# JTAG_DEBUG_HEADERS.net
KiCad netlist of a schematic drawn in Altium Designer
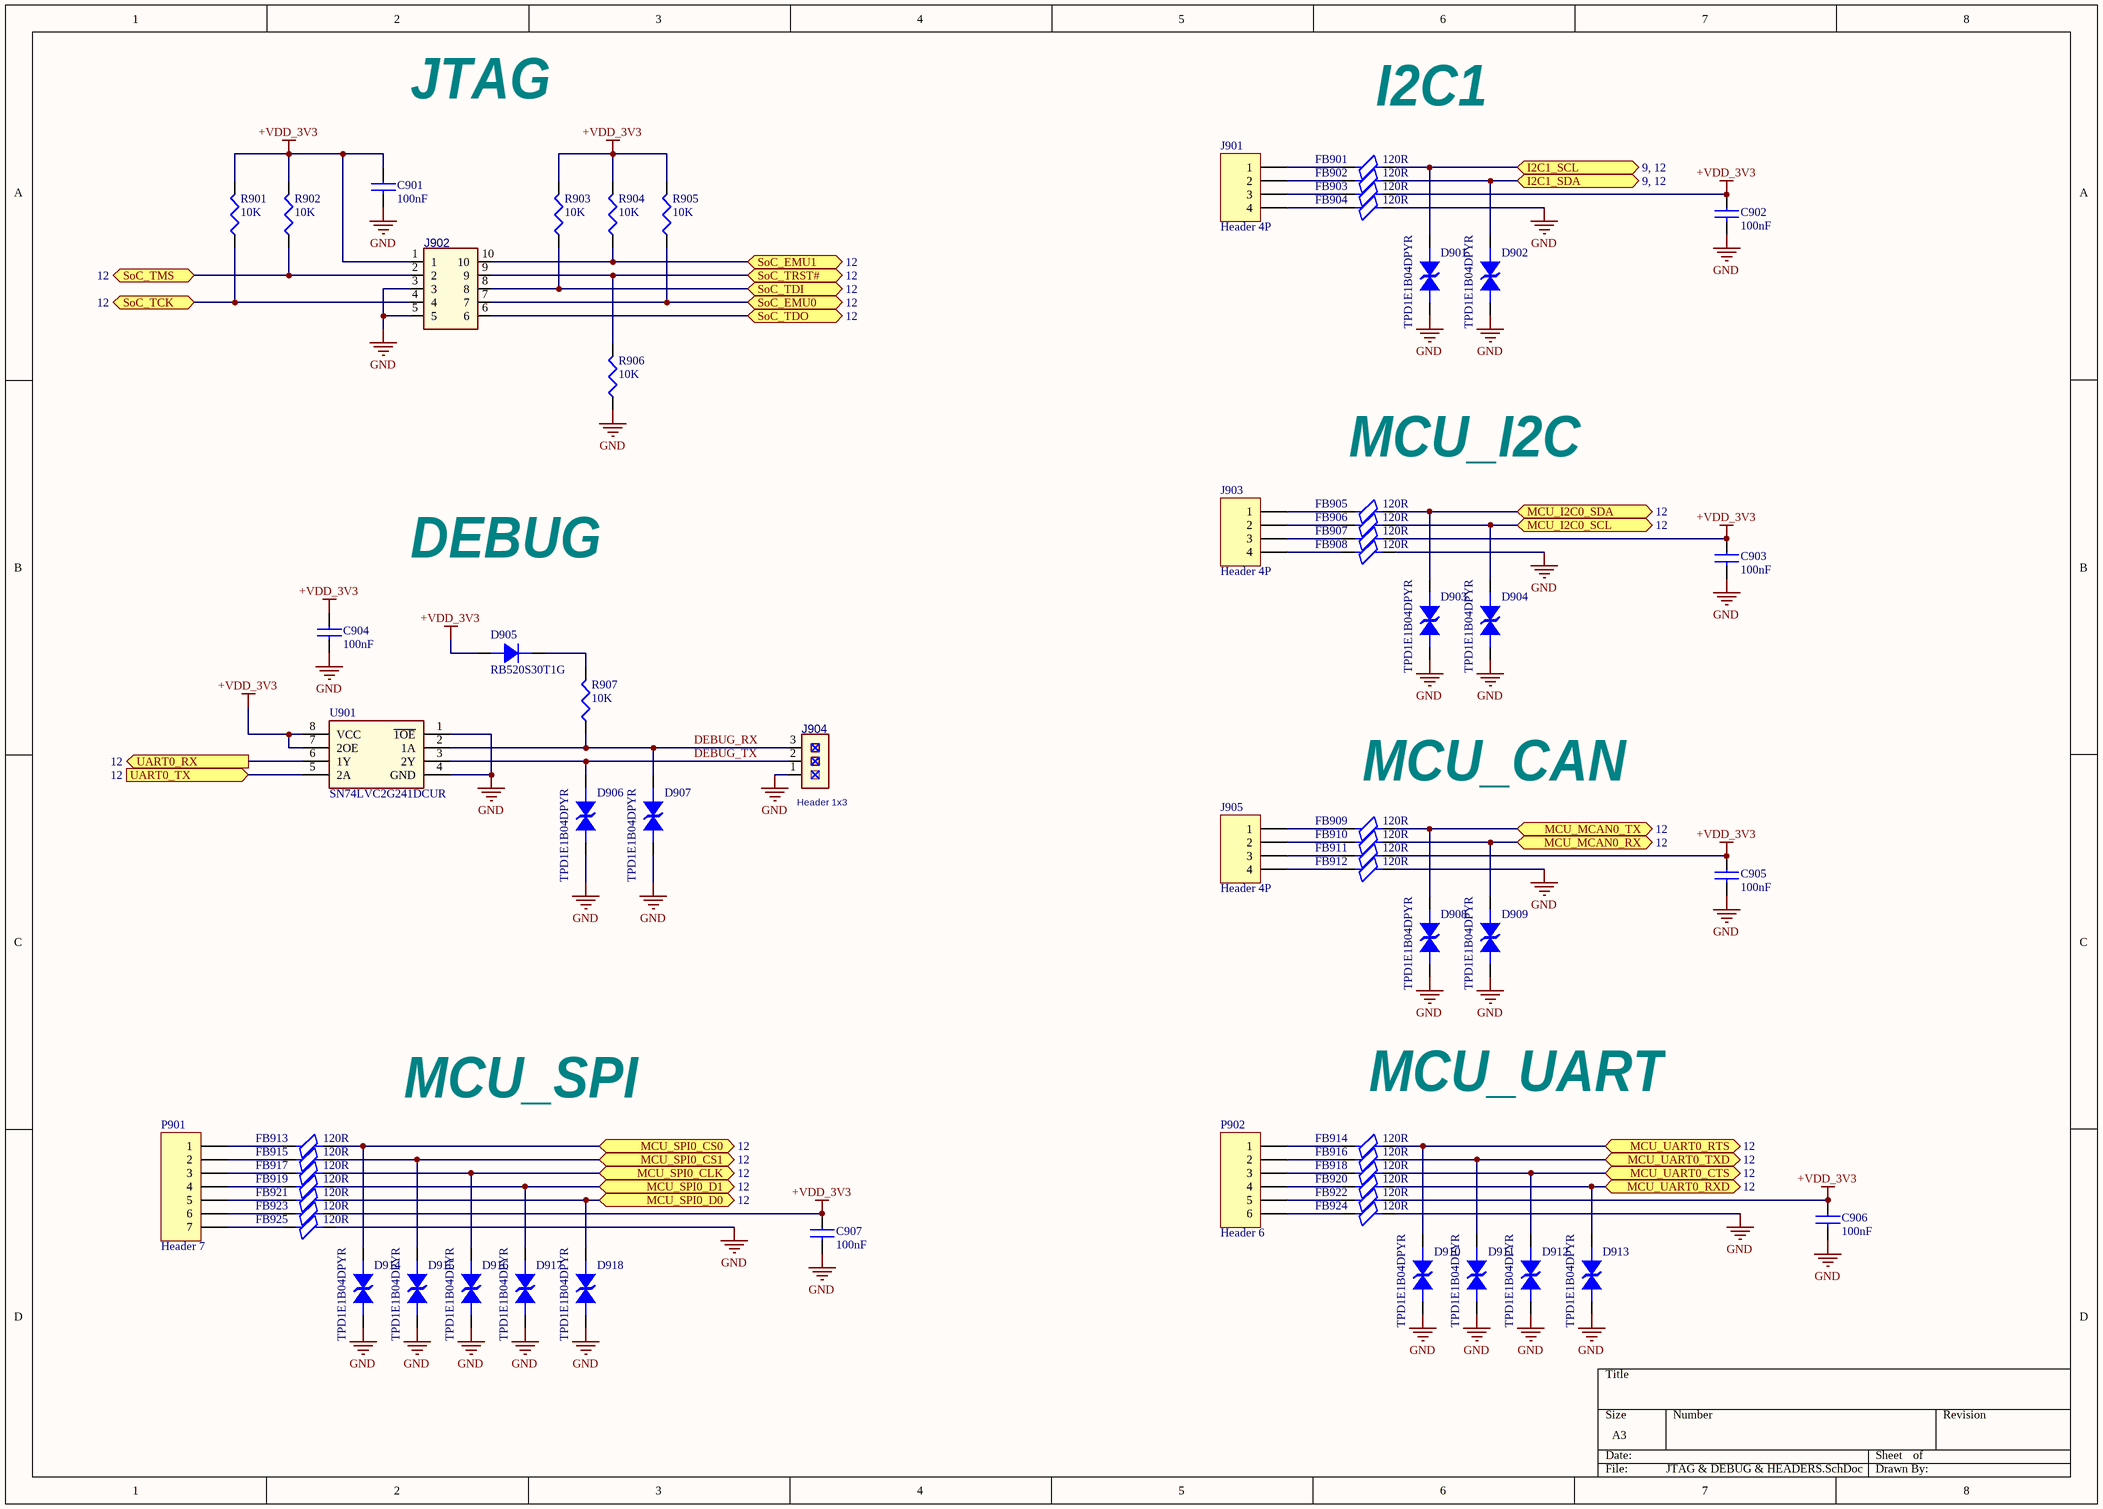
[diagram p0: JTAG & DEBUG & HEADERS.SchDoc]

(export (version "E")
  (design (tool "Eeschema 10.0.6"))
  (components
    (comp (ref "C901")
      (value "100nF")
      (footprint "C0201")
      (description "Multilayer Ceramic Capacitor, 0.1 uF, 16 V, ± 10%, X5R, 0201 [0603 Metric]")
      (fields
        (field (name "MANUFACTURER") "Yageo")
        (field (name "MANUFACTURER PART NUMBER") "CC0201KRX5R6BB104")
      )
      (libsource (lib "Schlib SOM AM625") (part "CC0201KRX5R6BB104"))
    )
    (comp (ref "C902")
      (value "100nF")
      (footprint "C0201")
      (description "Multilayer Ceramic Capacitor, 0.1 uF, 16 V, ± 10%, X5R, 0201 [0603 Metric]")
      (fields
        (field (name "MANUFACTURER") "Yageo")
        (field (name "MANUFACTURER PART NUMBER") "CC0201KRX5R6BB104")
      )
      (libsource (lib "Schlib SOM AM625") (part "CC0201KRX5R6BB104"))
    )
    (comp (ref "C903")
      (value "100nF")
      (footprint "C0201")
      (description "Multilayer Ceramic Capacitor, 0.1 uF, 16 V, ± 10%, X5R, 0201 [0603 Metric]")
      (fields
        (field (name "MANUFACTURER") "Yageo")
        (field (name "MANUFACTURER PART NUMBER") "CC0201KRX5R6BB104")
      )
      (libsource (lib "Schlib SOM AM625") (part "CC0201KRX5R6BB104"))
    )
    (comp (ref "C904")
      (value "100nF")
      (footprint "C0201")
      (description "Multilayer Ceramic Capacitor, 0.1 uF, 16 V, ± 10%, X5R, 0201 [0603 Metric]")
      (fields
        (field (name "MANUFACTURER") "Yageo")
        (field (name "MANUFACTURER PART NUMBER") "CC0201KRX5R6BB104")
      )
      (libsource (lib "Schlib SOM AM625") (part "CC0201KRX5R6BB104"))
    )
    (comp (ref "C905")
      (value "100nF")
      (footprint "C0201")
      (description "Multilayer Ceramic Capacitor, 0.1 uF, 16 V, ± 10%, X5R, 0201 [0603 Metric]")
      (fields
        (field (name "MANUFACTURER") "Yageo")
        (field (name "MANUFACTURER PART NUMBER") "CC0201KRX5R6BB104")
      )
      (libsource (lib "Schlib SOM AM625") (part "CC0201KRX5R6BB104"))
    )
    (comp (ref "C906")
      (value "100nF")
      (footprint "C0201")
      (description "Multilayer Ceramic Capacitor, 0.1 uF, 16 V, ± 10%, X5R, 0201 [0603 Metric]")
      (fields
        (field (name "MANUFACTURER") "Yageo")
        (field (name "MANUFACTURER PART NUMBER") "CC0201KRX5R6BB104")
      )
      (libsource (lib "Schlib SOM AM625") (part "CC0201KRX5R6BB104"))
    )
    (comp (ref "C907")
      (value "100nF")
      (footprint "C0201")
      (description "Multilayer Ceramic Capacitor, 0.1 uF, 16 V, ± 10%, X5R, 0201 [0603 Metric]")
      (fields
        (field (name "MANUFACTURER") "Yageo")
        (field (name "MANUFACTURER PART NUMBER") "CC0201KRX5R6BB104")
      )
      (libsource (lib "Schlib SOM AM625") (part "CC0201KRX5R6BB104"))
    )
    (comp (ref "D901")
      (value "TPD1E1B04DPYR")
      (footprint "DIO_TPD1E05U06DPYR")
      (description "1-pF, ±3.6-V, ±30-kV ESD protection diode with 6-A 8/20-uS surge & Low Clamping in 0402 package")
      (fields (field (name "MANUFACTURER") "Texas Instruments"))
      (libsource (lib "Schlib SOM AM625") (part "TPD1E1B04DPYR"))
    )
    (comp (ref "D902")
      (value "TPD1E1B04DPYR")
      (footprint "DIO_TPD1E05U06DPYR")
      (description "1-pF, ±3.6-V, ±30-kV ESD protection diode with 6-A 8/20-uS surge & Low Clamping in 0402 package")
      (fields (field (name "MANUFACTURER") "Texas Instruments"))
      (libsource (lib "Schlib SOM AM625") (part "TPD1E1B04DPYR"))
    )
    (comp (ref "D903")
      (value "TPD1E1B04DPYR")
      (footprint "DIO_TPD1E05U06DPYR")
      (description "1-pF, ±3.6-V, ±30-kV ESD protection diode with 6-A 8/20-uS surge & Low Clamping in 0402 package")
      (fields (field (name "MANUFACTURER") "Texas Instruments"))
      (libsource (lib "Schlib SOM AM625") (part "TPD1E1B04DPYR"))
    )
    (comp (ref "D904")
      (value "TPD1E1B04DPYR")
      (footprint "DIO_TPD1E05U06DPYR")
      (description "1-pF, ±3.6-V, ±30-kV ESD protection diode with 6-A 8/20-uS surge & Low Clamping in 0402 package")
      (fields (field (name "MANUFACTURER") "Texas Instruments"))
      (libsource (lib "Schlib SOM AM625") (part "TPD1E1B04DPYR"))
    )
    (comp (ref "D905")
      (value "RB520S30T1G")
      (footprint "sod_523")
      (description "Diode Schottky 30V 0.2A 2-Pin SOD-523 T/R - Product that comes on tape, but is not reeled")
      (fields (field (name "MANUFACTURER") "ON Semiconductor"))
      (libsource (lib "Schlib SOM AM625") (part "RB520S30T1G"))
    )
    (comp (ref "D906")
      (value "TPD1E1B04DPYR")
      (footprint "DIO_TPD1E05U06DPYR")
      (description "1-pF, ±3.6-V, ±30-kV ESD protection diode with 6-A 8/20-uS surge & Low Clamping in 0402 package")
      (fields (field (name "MANUFACTURER") "Texas Instruments"))
      (libsource (lib "Schlib SOM AM625") (part "TPD1E1B04DPYR"))
    )
    (comp (ref "D907")
      (value "TPD1E1B04DPYR")
      (footprint "DIO_TPD1E05U06DPYR")
      (description "1-pF, ±3.6-V, ±30-kV ESD protection diode with 6-A 8/20-uS surge & Low Clamping in 0402 package")
      (fields (field (name "MANUFACTURER") "Texas Instruments"))
      (libsource (lib "Schlib SOM AM625") (part "TPD1E1B04DPYR"))
    )
    (comp (ref "D908")
      (value "TPD1E1B04DPYR")
      (footprint "DIO_TPD1E05U06DPYR")
      (description "1-pF, ±3.6-V, ±30-kV ESD protection diode with 6-A 8/20-uS surge & Low Clamping in 0402 package")
      (fields (field (name "MANUFACTURER") "Texas Instruments"))
      (libsource (lib "Schlib SOM AM625") (part "TPD1E1B04DPYR"))
    )
    (comp (ref "D909")
      (value "TPD1E1B04DPYR")
      (footprint "DIO_TPD1E05U06DPYR")
      (description "1-pF, ±3.6-V, ±30-kV ESD protection diode with 6-A 8/20-uS surge & Low Clamping in 0402 package")
      (fields (field (name "MANUFACTURER") "Texas Instruments"))
      (libsource (lib "Schlib SOM AM625") (part "TPD1E1B04DPYR"))
    )
    (comp (ref "D910")
      (value "TPD1E1B04DPYR")
      (footprint "DIO_TPD1E05U06DPYR")
      (description "1-pF, ±3.6-V, ±30-kV ESD protection diode with 6-A 8/20-uS surge & Low Clamping in 0402 package")
      (fields (field (name "MANUFACTURER") "Texas Instruments"))
      (libsource (lib "Schlib SOM AM625") (part "TPD1E1B04DPYR"))
    )
    (comp (ref "D911")
      (value "TPD1E1B04DPYR")
      (footprint "DIO_TPD1E05U06DPYR")
      (description "1-pF, ±3.6-V, ±30-kV ESD protection diode with 6-A 8/20-uS surge & Low Clamping in 0402 package")
      (fields (field (name "MANUFACTURER") "Texas Instruments"))
      (libsource (lib "Schlib SOM AM625") (part "TPD1E1B04DPYR"))
    )
    (comp (ref "D912")
      (value "TPD1E1B04DPYR")
      (footprint "DIO_TPD1E05U06DPYR")
      (description "1-pF, ±3.6-V, ±30-kV ESD protection diode with 6-A 8/20-uS surge & Low Clamping in 0402 package")
      (fields (field (name "MANUFACTURER") "Texas Instruments"))
      (libsource (lib "Schlib SOM AM625") (part "TPD1E1B04DPYR"))
    )
    (comp (ref "D913")
      (value "TPD1E1B04DPYR")
      (footprint "DIO_TPD1E05U06DPYR")
      (description "1-pF, ±3.6-V, ±30-kV ESD protection diode with 6-A 8/20-uS surge & Low Clamping in 0402 package")
      (fields (field (name "MANUFACTURER") "Texas Instruments"))
      (libsource (lib "Schlib SOM AM625") (part "TPD1E1B04DPYR"))
    )
    (comp (ref "D914")
      (value "TPD1E1B04DPYR")
      (footprint "DIO_TPD1E05U06DPYR")
      (description "1-pF, ±3.6-V, ±30-kV ESD protection diode with 6-A 8/20-uS surge & Low Clamping in 0402 package")
      (fields (field (name "MANUFACTURER") "Texas Instruments"))
      (libsource (lib "Schlib SOM AM625") (part "TPD1E1B04DPYR"))
    )
    (comp (ref "D915")
      (value "TPD1E1B04DPYR")
      (footprint "DIO_TPD1E05U06DPYR")
      (description "1-pF, ±3.6-V, ±30-kV ESD protection diode with 6-A 8/20-uS surge & Low Clamping in 0402 package")
      (fields (field (name "MANUFACTURER") "Texas Instruments"))
      (libsource (lib "Schlib SOM AM625") (part "TPD1E1B04DPYR"))
    )
    (comp (ref "D916")
      (value "TPD1E1B04DPYR")
      (footprint "DIO_TPD1E05U06DPYR")
      (description "1-pF, ±3.6-V, ±30-kV ESD protection diode with 6-A 8/20-uS surge & Low Clamping in 0402 package")
      (fields (field (name "MANUFACTURER") "Texas Instruments"))
      (libsource (lib "Schlib SOM AM625") (part "TPD1E1B04DPYR"))
    )
    (comp (ref "D917")
      (value "TPD1E1B04DPYR")
      (footprint "DIO_TPD1E05U06DPYR")
      (description "1-pF, ±3.6-V, ±30-kV ESD protection diode with 6-A 8/20-uS surge & Low Clamping in 0402 package")
      (fields (field (name "MANUFACTURER") "Texas Instruments"))
      (libsource (lib "Schlib SOM AM625") (part "TPD1E1B04DPYR"))
    )
    (comp (ref "D918")
      (value "TPD1E1B04DPYR")
      (footprint "DIO_TPD1E05U06DPYR")
      (description "1-pF, ±3.6-V, ±30-kV ESD protection diode with 6-A 8/20-uS surge & Low Clamping in 0402 package")
      (fields (field (name "MANUFACTURER") "Texas Instruments"))
      (libsource (lib "Schlib SOM AM625") (part "TPD1E1B04DPYR"))
    )
    (comp (ref "FB901")
      (value "120R")
      (footprint "FB0402")
      (description "Ferrite Beads Multi-Layer 120Ohm 25% 100MHz 1.3A 0.09Ohm DCR 0402 Automotive T/R")
      (fields
        (field (name "MANUFACTURER") "Murata")
        (field (name "MANUFACTURER PART NUMBER") "BLM15PD121SZ1D")
      )
      (libsource (lib "Schlib SOM AM625") (part "BLM15PD121SZ1D"))
    )
    (comp (ref "FB902")
      (value "120R")
      (footprint "FB0402")
      (description "Ferrite Beads Multi-Layer 120Ohm 25% 100MHz 1.3A 0.09Ohm DCR 0402 Automotive T/R")
      (fields
        (field (name "MANUFACTURER") "Murata")
        (field (name "MANUFACTURER PART NUMBER") "BLM15PD121SZ1D")
      )
      (libsource (lib "Schlib SOM AM625") (part "BLM15PD121SZ1D"))
    )
    (comp (ref "FB903")
      (value "120R")
      (footprint "FB0402")
      (description "Ferrite Beads Multi-Layer 120Ohm 25% 100MHz 1.3A 0.09Ohm DCR 0402 Automotive T/R")
      (fields
        (field (name "MANUFACTURER") "Murata")
        (field (name "MANUFACTURER PART NUMBER") "BLM15PD121SZ1D")
      )
      (libsource (lib "Schlib SOM AM625") (part "BLM15PD121SZ1D"))
    )
    (comp (ref "FB904")
      (value "120R")
      (footprint "FB0402")
      (description "Ferrite Beads Multi-Layer 120Ohm 25% 100MHz 1.3A 0.09Ohm DCR 0402 Automotive T/R")
      (fields
        (field (name "MANUFACTURER") "Murata")
        (field (name "MANUFACTURER PART NUMBER") "BLM15PD121SZ1D")
      )
      (libsource (lib "Schlib SOM AM625") (part "BLM15PD121SZ1D"))
    )
    (comp (ref "FB905")
      (value "120R")
      (footprint "FB0402")
      (description "Ferrite Beads Multi-Layer 120Ohm 25% 100MHz 1.3A 0.09Ohm DCR 0402 Automotive T/R")
      (fields
        (field (name "MANUFACTURER") "Murata")
        (field (name "MANUFACTURER PART NUMBER") "BLM15PD121SZ1D")
      )
      (libsource (lib "Schlib SOM AM625") (part "BLM15PD121SZ1D"))
    )
    (comp (ref "FB906")
      (value "120R")
      (footprint "FB0402")
      (description "Ferrite Beads Multi-Layer 120Ohm 25% 100MHz 1.3A 0.09Ohm DCR 0402 Automotive T/R")
      (fields
        (field (name "MANUFACTURER") "Murata")
        (field (name "MANUFACTURER PART NUMBER") "BLM15PD121SZ1D")
      )
      (libsource (lib "Schlib SOM AM625") (part "BLM15PD121SZ1D"))
    )
    (comp (ref "FB907")
      (value "120R")
      (footprint "FB0402")
      (description "Ferrite Beads Multi-Layer 120Ohm 25% 100MHz 1.3A 0.09Ohm DCR 0402 Automotive T/R")
      (fields
        (field (name "MANUFACTURER") "Murata")
        (field (name "MANUFACTURER PART NUMBER") "BLM15PD121SZ1D")
      )
      (libsource (lib "Schlib SOM AM625") (part "BLM15PD121SZ1D"))
    )
    (comp (ref "FB908")
      (value "120R")
      (footprint "FB0402")
      (description "Ferrite Beads Multi-Layer 120Ohm 25% 100MHz 1.3A 0.09Ohm DCR 0402 Automotive T/R")
      (fields
        (field (name "MANUFACTURER") "Murata")
        (field (name "MANUFACTURER PART NUMBER") "BLM15PD121SZ1D")
      )
      (libsource (lib "Schlib SOM AM625") (part "BLM15PD121SZ1D"))
    )
    (comp (ref "FB909")
      (value "120R")
      (footprint "FB0402")
      (description "Ferrite Beads Multi-Layer 120Ohm 25% 100MHz 1.3A 0.09Ohm DCR 0402 Automotive T/R")
      (fields
        (field (name "MANUFACTURER") "Murata")
        (field (name "MANUFACTURER PART NUMBER") "BLM15PD121SZ1D")
      )
      (libsource (lib "Schlib SOM AM625") (part "BLM15PD121SZ1D"))
    )
    (comp (ref "FB910")
      (value "120R")
      (footprint "FB0402")
      (description "Ferrite Beads Multi-Layer 120Ohm 25% 100MHz 1.3A 0.09Ohm DCR 0402 Automotive T/R")
      (fields
        (field (name "MANUFACTURER") "Murata")
        (field (name "MANUFACTURER PART NUMBER") "BLM15PD121SZ1D")
      )
      (libsource (lib "Schlib SOM AM625") (part "BLM15PD121SZ1D"))
    )
    (comp (ref "FB911")
      (value "120R")
      (footprint "FB0402")
      (description "Ferrite Beads Multi-Layer 120Ohm 25% 100MHz 1.3A 0.09Ohm DCR 0402 Automotive T/R")
      (fields
        (field (name "MANUFACTURER") "Murata")
        (field (name "MANUFACTURER PART NUMBER") "BLM15PD121SZ1D")
      )
      (libsource (lib "Schlib SOM AM625") (part "BLM15PD121SZ1D"))
    )
    (comp (ref "FB912")
      (value "120R")
      (footprint "FB0402")
      (description "Ferrite Beads Multi-Layer 120Ohm 25% 100MHz 1.3A 0.09Ohm DCR 0402 Automotive T/R")
      (fields
        (field (name "MANUFACTURER") "Murata")
        (field (name "MANUFACTURER PART NUMBER") "BLM15PD121SZ1D")
      )
      (libsource (lib "Schlib SOM AM625") (part "BLM15PD121SZ1D"))
    )
    (comp (ref "FB913")
      (value "120R")
      (footprint "FB0402")
      (description "Ferrite Beads Multi-Layer 120Ohm 25% 100MHz 1.3A 0.09Ohm DCR 0402 Automotive T/R")
      (fields
        (field (name "MANUFACTURER") "Murata")
        (field (name "MANUFACTURER PART NUMBER") "BLM15PD121SZ1D")
      )
      (libsource (lib "Schlib SOM AM625") (part "BLM15PD121SZ1D"))
    )
    (comp (ref "FB914")
      (value "120R")
      (footprint "FB0402")
      (description "Ferrite Beads Multi-Layer 120Ohm 25% 100MHz 1.3A 0.09Ohm DCR 0402 Automotive T/R")
      (fields
        (field (name "MANUFACTURER") "Murata")
        (field (name "MANUFACTURER PART NUMBER") "BLM15PD121SZ1D")
      )
      (libsource (lib "Schlib SOM AM625") (part "BLM15PD121SZ1D"))
    )
    (comp (ref "FB915")
      (value "120R")
      (footprint "FB0402")
      (description "Ferrite Beads Multi-Layer 120Ohm 25% 100MHz 1.3A 0.09Ohm DCR 0402 Automotive T/R")
      (fields
        (field (name "MANUFACTURER") "Murata")
        (field (name "MANUFACTURER PART NUMBER") "BLM15PD121SZ1D")
      )
      (libsource (lib "Schlib SOM AM625") (part "BLM15PD121SZ1D"))
    )
    (comp (ref "FB916")
      (value "120R")
      (footprint "FB0402")
      (description "Ferrite Beads Multi-Layer 120Ohm 25% 100MHz 1.3A 0.09Ohm DCR 0402 Automotive T/R")
      (fields
        (field (name "MANUFACTURER") "Murata")
        (field (name "MANUFACTURER PART NUMBER") "BLM15PD121SZ1D")
      )
      (libsource (lib "Schlib SOM AM625") (part "BLM15PD121SZ1D"))
    )
    (comp (ref "FB917")
      (value "120R")
      (footprint "FB0402")
      (description "Ferrite Beads Multi-Layer 120Ohm 25% 100MHz 1.3A 0.09Ohm DCR 0402 Automotive T/R")
      (fields
        (field (name "MANUFACTURER") "Murata")
        (field (name "MANUFACTURER PART NUMBER") "BLM15PD121SZ1D")
      )
      (libsource (lib "Schlib SOM AM625") (part "BLM15PD121SZ1D"))
    )
    (comp (ref "FB918")
      (value "120R")
      (footprint "FB0402")
      (description "Ferrite Beads Multi-Layer 120Ohm 25% 100MHz 1.3A 0.09Ohm DCR 0402 Automotive T/R")
      (fields
        (field (name "MANUFACTURER") "Murata")
        (field (name "MANUFACTURER PART NUMBER") "BLM15PD121SZ1D")
      )
      (libsource (lib "Schlib SOM AM625") (part "BLM15PD121SZ1D"))
    )
    (comp (ref "FB919")
      (value "120R")
      (footprint "FB0402")
      (description "Ferrite Beads Multi-Layer 120Ohm 25% 100MHz 1.3A 0.09Ohm DCR 0402 Automotive T/R")
      (fields
        (field (name "MANUFACTURER") "Murata")
        (field (name "MANUFACTURER PART NUMBER") "BLM15PD121SZ1D")
      )
      (libsource (lib "Schlib SOM AM625") (part "BLM15PD121SZ1D"))
    )
    (comp (ref "FB920")
      (value "120R")
      (footprint "FB0402")
      (description "Ferrite Beads Multi-Layer 120Ohm 25% 100MHz 1.3A 0.09Ohm DCR 0402 Automotive T/R")
      (fields
        (field (name "MANUFACTURER") "Murata")
        (field (name "MANUFACTURER PART NUMBER") "BLM15PD121SZ1D")
      )
      (libsource (lib "Schlib SOM AM625") (part "BLM15PD121SZ1D"))
    )
    (comp (ref "FB921")
      (value "120R")
      (footprint "FB0402")
      (description "Ferrite Beads Multi-Layer 120Ohm 25% 100MHz 1.3A 0.09Ohm DCR 0402 Automotive T/R")
      (fields
        (field (name "MANUFACTURER") "Murata")
        (field (name "MANUFACTURER PART NUMBER") "BLM15PD121SZ1D")
      )
      (libsource (lib "Schlib SOM AM625") (part "BLM15PD121SZ1D"))
    )
    (comp (ref "FB922")
      (value "120R")
      (footprint "FB0402")
      (description "Ferrite Beads Multi-Layer 120Ohm 25% 100MHz 1.3A 0.09Ohm DCR 0402 Automotive T/R")
      (fields
        (field (name "MANUFACTURER") "Murata")
        (field (name "MANUFACTURER PART NUMBER") "BLM15PD121SZ1D")
      )
      (libsource (lib "Schlib SOM AM625") (part "BLM15PD121SZ1D"))
    )
    (comp (ref "FB923")
      (value "120R")
      (footprint "FB0402")
      (description "Ferrite Beads Multi-Layer 120Ohm 25% 100MHz 1.3A 0.09Ohm DCR 0402 Automotive T/R")
      (fields
        (field (name "MANUFACTURER") "Murata")
        (field (name "MANUFACTURER PART NUMBER") "BLM15PD121SZ1D")
      )
      (libsource (lib "Schlib SOM AM625") (part "BLM15PD121SZ1D"))
    )
    (comp (ref "FB924")
      (value "120R")
      (footprint "FB0402")
      (description "Ferrite Beads Multi-Layer 120Ohm 25% 100MHz 1.3A 0.09Ohm DCR 0402 Automotive T/R")
      (fields
        (field (name "MANUFACTURER") "Murata")
        (field (name "MANUFACTURER PART NUMBER") "BLM15PD121SZ1D")
      )
      (libsource (lib "Schlib SOM AM625") (part "BLM15PD121SZ1D"))
    )
    (comp (ref "FB925")
      (value "120R")
      (footprint "FB0402")
      (description "Ferrite Beads Multi-Layer 120Ohm 25% 100MHz 1.3A 0.09Ohm DCR 0402 Automotive T/R")
      (fields
        (field (name "MANUFACTURER") "Murata")
        (field (name "MANUFACTURER PART NUMBER") "BLM15PD121SZ1D")
      )
      (libsource (lib "Schlib SOM AM625") (part "BLM15PD121SZ1D"))
    )
    (comp (ref "J901")
      (value "Header 4P")
      (footprint "HDR1X4")
      (description "Header, 4 Pin Pitch 2.54mm")
      (fields (field (name "MPN") "S1012EC-40-ND"))
      (libsource (lib "Schlib SOM AM625") (part "Header 4x1"))
    )
    (comp (ref "J902")
      (value "Header 2X5_1")
      (footprint "CONNECT10_1D27_12_4X6_7MM")
      (libsource (lib "Schlib SOM AM625") (part "Header 2X5_1"))
    )
    (comp (ref "J903")
      (value "Header 4P")
      (footprint "HDR1X4")
      (description "Header, 4 Pin Pitch 2.54mm")
      (fields (field (name "MPN") "S1012EC-40-ND"))
      (libsource (lib "Schlib SOM AM625") (part "Header 4x1"))
    )
    (comp (ref "J904")
      (value "Header 1x3")
      (footprint "HDR1X3")
      (libsource (lib "Schlib SOM AM625") (part "Header 1x3"))
    )
    (comp (ref "J905")
      (value "Header 4P")
      (footprint "HDR1X4")
      (description "Header, 4 Pin Pitch 2.54mm")
      (fields (field (name "MPN") "S1012EC-40-ND"))
      (libsource (lib "Schlib SOM AM625") (part "Header 4x1"))
    )
    (comp (ref "P901")
      (value "Header 7")
      (footprint "HDR1X7")
      (description "Header, 7-Pin, 2.54mm")
      (libsource (lib "Schlib SOM AM625") (part "Header 7x1"))
    )
    (comp (ref "P902")
      (value "Header 6")
      (footprint "HDR1X6")
      (description "Header, 6-Pin")
      (libsource (lib "Schlib SOM AM625") (part "Header 6x1"))
    )
    (comp (ref "R901")
      (value "10K")
      (footprint "R0402")
      (description "RES 10.0K OHM 1/16W 1% 0402 SMD")
      (fields
        (field (name "MANUFACTURER") "Yageo")
        (field (name "MANUFACTURER PART NUMBER") "RC0402FR-0710KL")
      )
      (libsource (lib "Schlib SOM AM625") (part "RC0402FR-0710KL"))
    )
    (comp (ref "R902")
      (value "10K")
      (footprint "R0402")
      (description "RES 10.0K OHM 1/16W 1% 0402 SMD")
      (fields
        (field (name "MANUFACTURER") "Yageo")
        (field (name "MANUFACTURER PART NUMBER") "RC0402FR-0710KL")
      )
      (libsource (lib "Schlib SOM AM625") (part "RC0402FR-0710KL"))
    )
    (comp (ref "R903")
      (value "10K")
      (footprint "R0402")
      (description "RES 10.0K OHM 1/16W 1% 0402 SMD")
      (fields
        (field (name "MANUFACTURER") "Yageo")
        (field (name "MANUFACTURER PART NUMBER") "RC0402FR-0710KL")
      )
      (libsource (lib "Schlib SOM AM625") (part "RC0402FR-0710KL"))
    )
    (comp (ref "R904")
      (value "10K")
      (footprint "R0402")
      (description "RES 10.0K OHM 1/16W 1% 0402 SMD")
      (fields
        (field (name "MANUFACTURER") "Yageo")
        (field (name "MANUFACTURER PART NUMBER") "RC0402FR-0710KL")
      )
      (libsource (lib "Schlib SOM AM625") (part "RC0402FR-0710KL"))
    )
    (comp (ref "R905")
      (value "10K")
      (footprint "R0402")
      (description "RES 10.0K OHM 1/16W 1% 0402 SMD")
      (fields
        (field (name "MANUFACTURER") "Yageo")
        (field (name "MANUFACTURER PART NUMBER") "RC0402FR-0710KL")
      )
      (libsource (lib "Schlib SOM AM625") (part "RC0402FR-0710KL"))
    )
    (comp (ref "R906")
      (value "10K")
      (footprint "R0402")
      (description "RES 10.0K OHM 1/16W 1% 0402 SMD")
      (fields
        (field (name "MANUFACTURER") "Yageo")
        (field (name "MANUFACTURER PART NUMBER") "RC0402FR-0710KL")
      )
      (libsource (lib "Schlib SOM AM625") (part "RC0402FR-0710KL"))
    )
    (comp (ref "R907")
      (value "10K")
      (footprint "R0402")
      (description "RES 10.0K OHM 1/16W 1% 0402 SMD")
      (fields
        (field (name "MANUFACTURER") "Yageo")
        (field (name "MANUFACTURER PART NUMBER") "RC0402FR-0710KL")
      )
      (libsource (lib "Schlib SOM AM625") (part "RC0402FR-0710KL"))
    )
    (comp (ref "U901")
      (value "SN74LVC2G241DCUR")
      (footprint "DCU8-M")
      (description "Buffer, Non-Inverting 2 Element 1 Bit per Element Push-Pull Output US8")
      (fields (field (name "MANUFACTURER") "Texas Instruments"))
      (libsource (lib "Schlib SOM AM625") (part "SN74LVC2G241DCUR"))
    )
  )
  (nets
    (net (code "1") (name "+VDD_3V3") (class "Default")
      (node (ref "C901") (pin "1") (pinfunction "1_1") (pintype "passive"))
      (node (ref "C902") (pin "1") (pinfunction "1_1") (pintype "passive"))
      (node (ref "C903") (pin "1") (pinfunction "1_1") (pintype "passive"))
      (node (ref "C904") (pin "1") (pinfunction "1_1") (pintype "passive"))
      (node (ref "C905") (pin "1") (pinfunction "1_1") (pintype "passive"))
      (node (ref "C906") (pin "1") (pinfunction "1_1") (pintype "passive"))
      (node (ref "C907") (pin "1") (pinfunction "1_1") (pintype "passive"))
      (node (ref "D905") (pin "1") (pinfunction "A_1") (pintype "passive"))
      (node (ref "FB903") (pin "2") (pinfunction "2_2") (pintype "passive"))
      (node (ref "FB907") (pin "2") (pinfunction "2_2") (pintype "passive"))
      (node (ref "FB911") (pin "2") (pinfunction "2_2") (pintype "passive"))
      (node (ref "FB922") (pin "2") (pinfunction "2_2") (pintype "passive"))
      (node (ref "FB923") (pin "2") (pinfunction "2_2") (pintype "passive"))
      (node (ref "J902") (pin "1") (pinfunction "1_1") (pintype "passive"))
      (node (ref "R901") (pin "2") (pinfunction "2_2") (pintype "passive"))
      (node (ref "R902") (pin "2") (pinfunction "2_2") (pintype "passive"))
      (node (ref "R903") (pin "2") (pinfunction "2_2") (pintype "passive"))
      (node (ref "R904") (pin "2") (pinfunction "2_2") (pintype "passive"))
      (node (ref "R905") (pin "2") (pinfunction "2_2") (pintype "passive"))
      (node (ref "U901") (pin "7") (pinfunction "2OE_7") (pintype "passive"))
      (node (ref "U901") (pin "8") (pinfunction "VCC_8") (pintype "power_in"))
    )
    (net (code "2") (name "/DEBUG_RX") (class "Default")
      (node (ref "D907") (pin "2") (pinfunction "2_2") (pintype "passive"))
      (node (ref "J904") (pin "3") (pinfunction "3_3") (pintype "passive"))
      (node (ref "R907") (pin "1") (pinfunction "1_1") (pintype "passive"))
      (node (ref "U901") (pin "2") (pinfunction "1A_2") (pintype "passive"))
    )
    (net (code "3") (name "/DEBUG_TX") (class "Default")
      (node (ref "D906") (pin "2") (pinfunction "2_2") (pintype "passive"))
      (node (ref "J904") (pin "2") (pinfunction "2_2") (pintype "passive"))
      (node (ref "U901") (pin "3") (pinfunction "2Y_3") (pintype "passive"))
    )
    (net (code "4") (name "/I2C1_SCL") (class "Default")
      (node (ref "D901") (pin "2") (pinfunction "2_2") (pintype "passive"))
      (node (ref "FB901") (pin "2") (pinfunction "2_2") (pintype "passive"))
    )
    (net (code "5") (name "/I2C1_SDA") (class "Default")
      (node (ref "D902") (pin "2") (pinfunction "2_2") (pintype "passive"))
      (node (ref "FB902") (pin "2") (pinfunction "2_2") (pintype "passive"))
    )
    (net (code "6") (name "/MCU_I2C0_SCL") (class "Default")
      (node (ref "D904") (pin "2") (pinfunction "2_2") (pintype "passive"))
      (node (ref "FB906") (pin "2") (pinfunction "2_2") (pintype "passive"))
    )
    (net (code "7") (name "/MCU_I2C0_SDA") (class "Default")
      (node (ref "D903") (pin "2") (pinfunction "2_2") (pintype "passive"))
      (node (ref "FB905") (pin "2") (pinfunction "2_2") (pintype "passive"))
    )
    (net (code "8") (name "/MCU_MCAN0_RX") (class "Default")
      (node (ref "D909") (pin "2") (pinfunction "2_2") (pintype "passive"))
      (node (ref "FB910") (pin "2") (pinfunction "2_2") (pintype "passive"))
    )
    (net (code "9") (name "/MCU_MCAN0_TX") (class "Default")
      (node (ref "D908") (pin "2") (pinfunction "2_2") (pintype "passive"))
      (node (ref "FB909") (pin "2") (pinfunction "2_2") (pintype "passive"))
    )
    (net (code "10") (name "/MCU_SPI0_CLK") (class "Default")
      (node (ref "D916") (pin "2") (pinfunction "2_2") (pintype "passive"))
      (node (ref "FB917") (pin "2") (pinfunction "2_2") (pintype "passive"))
    )
    (net (code "11") (name "/MCU_SPI0_CS0") (class "Default")
      (node (ref "D914") (pin "2") (pinfunction "2_2") (pintype "passive"))
      (node (ref "FB913") (pin "2") (pinfunction "2_2") (pintype "passive"))
    )
    (net (code "12") (name "/MCU_SPI0_CS1") (class "Default")
      (node (ref "D915") (pin "2") (pinfunction "2_2") (pintype "passive"))
      (node (ref "FB915") (pin "2") (pinfunction "2_2") (pintype "passive"))
    )
    (net (code "13") (name "/MCU_SPI0_D0") (class "Default")
      (node (ref "D918") (pin "2") (pinfunction "2_2") (pintype "passive"))
      (node (ref "FB921") (pin "2") (pinfunction "2_2") (pintype "passive"))
    )
    (net (code "14") (name "/MCU_SPI0_D1") (class "Default")
      (node (ref "D917") (pin "2") (pinfunction "2_2") (pintype "passive"))
      (node (ref "FB919") (pin "2") (pinfunction "2_2") (pintype "passive"))
    )
    (net (code "15") (name "/MCU_UART0_CTS") (class "Default")
      (node (ref "D912") (pin "2") (pinfunction "2_2") (pintype "passive"))
      (node (ref "FB918") (pin "2") (pinfunction "2_2") (pintype "passive"))
    )
    (net (code "16") (name "/MCU_UART0_RTS") (class "Default")
      (node (ref "D910") (pin "2") (pinfunction "2_2") (pintype "passive"))
      (node (ref "FB914") (pin "2") (pinfunction "2_2") (pintype "passive"))
    )
    (net (code "17") (name "/MCU_UART0_RXD") (class "Default")
      (node (ref "D913") (pin "2") (pinfunction "2_2") (pintype "passive"))
      (node (ref "FB920") (pin "2") (pinfunction "2_2") (pintype "passive"))
    )
    (net (code "18") (name "/MCU_UART0_TXD") (class "Default")
      (node (ref "D911") (pin "2") (pinfunction "2_2") (pintype "passive"))
      (node (ref "FB916") (pin "2") (pinfunction "2_2") (pintype "passive"))
    )
    (net (code "19") (name "/SoC_EMU0") (class "Default")
      (node (ref "J902") (pin "7") (pinfunction "7_7") (pintype "passive"))
      (node (ref "R905") (pin "1") (pinfunction "1_1") (pintype "passive"))
    )
    (net (code "20") (name "/SoC_EMU1") (class "Default")
      (node (ref "J902") (pin "10") (pinfunction "10_10") (pintype "passive"))
      (node (ref "R904") (pin "1") (pinfunction "1_1") (pintype "passive"))
    )
    (net (code "21") (name "/SoC_TCK") (class "Default")
      (node (ref "J902") (pin "4") (pinfunction "4_4") (pintype "passive"))
      (node (ref "R901") (pin "1") (pinfunction "1_1") (pintype "passive"))
    )
    (net (code "22") (name "/SoC_TDI") (class "Default")
      (node (ref "J902") (pin "8") (pinfunction "8_8") (pintype "passive"))
      (node (ref "R903") (pin "1") (pinfunction "1_1") (pintype "passive"))
    )
    (net (code "23") (name "/SoC_TDO") (class "Default")
      (node (ref "J902") (pin "6") (pinfunction "6_6") (pintype "passive"))
    )
    (net (code "24") (name "/SoC_TMS") (class "Default")
      (node (ref "J902") (pin "2") (pinfunction "2_2") (pintype "passive"))
      (node (ref "R902") (pin "1") (pinfunction "1_1") (pintype "passive"))
    )
    (net (code "25") (name "/SoC_TRST#") (class "Default")
      (node (ref "J902") (pin "9") (pinfunction "9_9") (pintype "passive"))
      (node (ref "R906") (pin "2") (pinfunction "2_2") (pintype "passive"))
    )
    (net (code "26") (name "/UART0_RX") (class "Default")
      (node (ref "U901") (pin "6") (pinfunction "1Y_6") (pintype "passive"))
    )
    (net (code "27") (name "/UART0_TX") (class "Default")
      (node (ref "U901") (pin "5") (pinfunction "2A_5") (pintype "passive"))
    )
    (net (code "28") (name "GND") (class "Default")
      (node (ref "C901") (pin "2") (pinfunction "2_2") (pintype "passive"))
      (node (ref "C902") (pin "2") (pinfunction "2_2") (pintype "passive"))
      (node (ref "C903") (pin "2") (pinfunction "2_2") (pintype "passive"))
      (node (ref "C904") (pin "2") (pinfunction "2_2") (pintype "passive"))
      (node (ref "C905") (pin "2") (pinfunction "2_2") (pintype "passive"))
      (node (ref "C906") (pin "2") (pinfunction "2_2") (pintype "passive"))
      (node (ref "C907") (pin "2") (pinfunction "2_2") (pintype "passive"))
      (node (ref "D901") (pin "1") (pinfunction "1_1") (pintype "passive"))
      (node (ref "D902") (pin "1") (pinfunction "1_1") (pintype "passive"))
      (node (ref "D903") (pin "1") (pinfunction "1_1") (pintype "passive"))
      (node (ref "D904") (pin "1") (pinfunction "1_1") (pintype "passive"))
      (node (ref "D906") (pin "1") (pinfunction "1_1") (pintype "passive"))
      (node (ref "D907") (pin "1") (pinfunction "1_1") (pintype "passive"))
      (node (ref "D908") (pin "1") (pinfunction "1_1") (pintype "passive"))
      (node (ref "D909") (pin "1") (pinfunction "1_1") (pintype "passive"))
      (node (ref "D910") (pin "1") (pinfunction "1_1") (pintype "passive"))
      (node (ref "D911") (pin "1") (pinfunction "1_1") (pintype "passive"))
      (node (ref "D912") (pin "1") (pinfunction "1_1") (pintype "passive"))
      (node (ref "D913") (pin "1") (pinfunction "1_1") (pintype "passive"))
      (node (ref "D914") (pin "1") (pinfunction "1_1") (pintype "passive"))
      (node (ref "D915") (pin "1") (pinfunction "1_1") (pintype "passive"))
      (node (ref "D916") (pin "1") (pinfunction "1_1") (pintype "passive"))
      (node (ref "D917") (pin "1") (pinfunction "1_1") (pintype "passive"))
      (node (ref "D918") (pin "1") (pinfunction "1_1") (pintype "passive"))
      (node (ref "FB904") (pin "2") (pinfunction "2_2") (pintype "passive"))
      (node (ref "FB908") (pin "2") (pinfunction "2_2") (pintype "passive"))
      (node (ref "FB912") (pin "2") (pinfunction "2_2") (pintype "passive"))
      (node (ref "FB924") (pin "2") (pinfunction "2_2") (pintype "passive"))
      (node (ref "FB925") (pin "2") (pinfunction "2_2") (pintype "passive"))
      (node (ref "J902") (pin "3") (pinfunction "3_3") (pintype "passive"))
      (node (ref "J902") (pin "5") (pinfunction "5_5") (pintype "passive"))
      (node (ref "J904") (pin "1") (pinfunction "1_1") (pintype "passive"))
      (node (ref "R906") (pin "1") (pinfunction "1_1") (pintype "passive"))
      (node (ref "U901") (pin "1") (pinfunction "~{1OE}_1") (pintype "passive"))
      (node (ref "U901") (pin "4") (pinfunction "GND_4") (pintype "power_in"))
    )
    (net (code "29") (name "Net-(D905-C)") (class "Default")
      (node (ref "D905") (pin "2") (pinfunction "C_2") (pintype "passive"))
      (node (ref "R907") (pin "2") (pinfunction "2_2") (pintype "passive"))
    )
    (net (code "30") (name "Net-(FB901-Pad1)") (class "Default")
      (node (ref "FB901") (pin "1") (pinfunction "1_1") (pintype "passive"))
      (node (ref "J901") (pin "1") (pinfunction "1_1") (pintype "passive"))
    )
    (net (code "31") (name "Net-(FB902-Pad1)") (class "Default")
      (node (ref "FB902") (pin "1") (pinfunction "1_1") (pintype "passive"))
      (node (ref "J901") (pin "2") (pinfunction "2_2") (pintype "passive"))
    )
    (net (code "32") (name "Net-(FB903-Pad1)") (class "Default")
      (node (ref "FB903") (pin "1") (pinfunction "1_1") (pintype "passive"))
      (node (ref "J901") (pin "3") (pinfunction "3_3") (pintype "passive"))
    )
    (net (code "33") (name "Net-(FB904-Pad1)") (class "Default")
      (node (ref "FB904") (pin "1") (pinfunction "1_1") (pintype "passive"))
      (node (ref "J901") (pin "4") (pinfunction "4_4") (pintype "passive"))
    )
    (net (code "34") (name "Net-(FB905-Pad1)") (class "Default")
      (node (ref "FB905") (pin "1") (pinfunction "1_1") (pintype "passive"))
      (node (ref "J903") (pin "1") (pinfunction "1_1") (pintype "passive"))
    )
    (net (code "35") (name "Net-(FB906-Pad1)") (class "Default")
      (node (ref "FB906") (pin "1") (pinfunction "1_1") (pintype "passive"))
      (node (ref "J903") (pin "2") (pinfunction "2_2") (pintype "passive"))
    )
    (net (code "36") (name "Net-(FB907-Pad1)") (class "Default")
      (node (ref "FB907") (pin "1") (pinfunction "1_1") (pintype "passive"))
      (node (ref "J903") (pin "3") (pinfunction "3_3") (pintype "passive"))
    )
    (net (code "37") (name "Net-(FB908-Pad1)") (class "Default")
      (node (ref "FB908") (pin "1") (pinfunction "1_1") (pintype "passive"))
      (node (ref "J903") (pin "4") (pinfunction "4_4") (pintype "passive"))
    )
    (net (code "38") (name "Net-(FB909-Pad1)") (class "Default")
      (node (ref "FB909") (pin "1") (pinfunction "1_1") (pintype "passive"))
      (node (ref "J905") (pin "1") (pinfunction "1_1") (pintype "passive"))
    )
    (net (code "39") (name "Net-(FB910-Pad1)") (class "Default")
      (node (ref "FB910") (pin "1") (pinfunction "1_1") (pintype "passive"))
      (node (ref "J905") (pin "2") (pinfunction "2_2") (pintype "passive"))
    )
    (net (code "40") (name "Net-(FB911-Pad1)") (class "Default")
      (node (ref "FB911") (pin "1") (pinfunction "1_1") (pintype "passive"))
      (node (ref "J905") (pin "3") (pinfunction "3_3") (pintype "passive"))
    )
    (net (code "41") (name "Net-(FB912-Pad1)") (class "Default")
      (node (ref "FB912") (pin "1") (pinfunction "1_1") (pintype "passive"))
      (node (ref "J905") (pin "4") (pinfunction "4_4") (pintype "passive"))
    )
    (net (code "42") (name "Net-(FB913-Pad1)") (class "Default")
      (node (ref "FB913") (pin "1") (pinfunction "1_1") (pintype "passive"))
      (node (ref "P901") (pin "1") (pinfunction "1_1") (pintype "passive"))
    )
    (net (code "43") (name "Net-(FB914-Pad1)") (class "Default")
      (node (ref "FB914") (pin "1") (pinfunction "1_1") (pintype "passive"))
      (node (ref "P902") (pin "1") (pinfunction "1_1") (pintype "passive"))
    )
    (net (code "44") (name "Net-(FB915-Pad1)") (class "Default")
      (node (ref "FB915") (pin "1") (pinfunction "1_1") (pintype "passive"))
      (node (ref "P901") (pin "2") (pinfunction "2_2") (pintype "passive"))
    )
    (net (code "45") (name "Net-(FB916-Pad1)") (class "Default")
      (node (ref "FB916") (pin "1") (pinfunction "1_1") (pintype "passive"))
      (node (ref "P902") (pin "2") (pinfunction "2_2") (pintype "passive"))
    )
    (net (code "46") (name "Net-(FB917-Pad1)") (class "Default")
      (node (ref "FB917") (pin "1") (pinfunction "1_1") (pintype "passive"))
      (node (ref "P901") (pin "3") (pinfunction "3_3") (pintype "passive"))
    )
    (net (code "47") (name "Net-(FB918-Pad1)") (class "Default")
      (node (ref "FB918") (pin "1") (pinfunction "1_1") (pintype "passive"))
      (node (ref "P902") (pin "3") (pinfunction "3_3") (pintype "passive"))
    )
    (net (code "48") (name "Net-(FB919-Pad1)") (class "Default")
      (node (ref "FB919") (pin "1") (pinfunction "1_1") (pintype "passive"))
      (node (ref "P901") (pin "4") (pinfunction "4_4") (pintype "passive"))
    )
    (net (code "49") (name "Net-(FB920-Pad1)") (class "Default")
      (node (ref "FB920") (pin "1") (pinfunction "1_1") (pintype "passive"))
      (node (ref "P902") (pin "4") (pinfunction "4_4") (pintype "passive"))
    )
    (net (code "50") (name "Net-(FB921-Pad1)") (class "Default")
      (node (ref "FB921") (pin "1") (pinfunction "1_1") (pintype "passive"))
      (node (ref "P901") (pin "5") (pinfunction "5_5") (pintype "passive"))
    )
    (net (code "51") (name "Net-(FB922-Pad1)") (class "Default")
      (node (ref "FB922") (pin "1") (pinfunction "1_1") (pintype "passive"))
      (node (ref "P902") (pin "5") (pinfunction "5_5") (pintype "passive"))
    )
    (net (code "52") (name "Net-(FB923-Pad1)") (class "Default")
      (node (ref "FB923") (pin "1") (pinfunction "1_1") (pintype "passive"))
      (node (ref "P901") (pin "6") (pinfunction "6_6") (pintype "passive"))
    )
    (net (code "53") (name "Net-(FB924-Pad1)") (class "Default")
      (node (ref "FB924") (pin "1") (pinfunction "1_1") (pintype "passive"))
      (node (ref "P902") (pin "6") (pinfunction "6_6") (pintype "passive"))
    )
    (net (code "54") (name "Net-(FB925-Pad1)") (class "Default")
      (node (ref "FB925") (pin "1") (pinfunction "1_1") (pintype "passive"))
      (node (ref "P901") (pin "7") (pinfunction "7_7") (pintype "passive"))
    )
  )
)
